# untitled.net
KiCad netlist of a schematic drawn in EAGLE
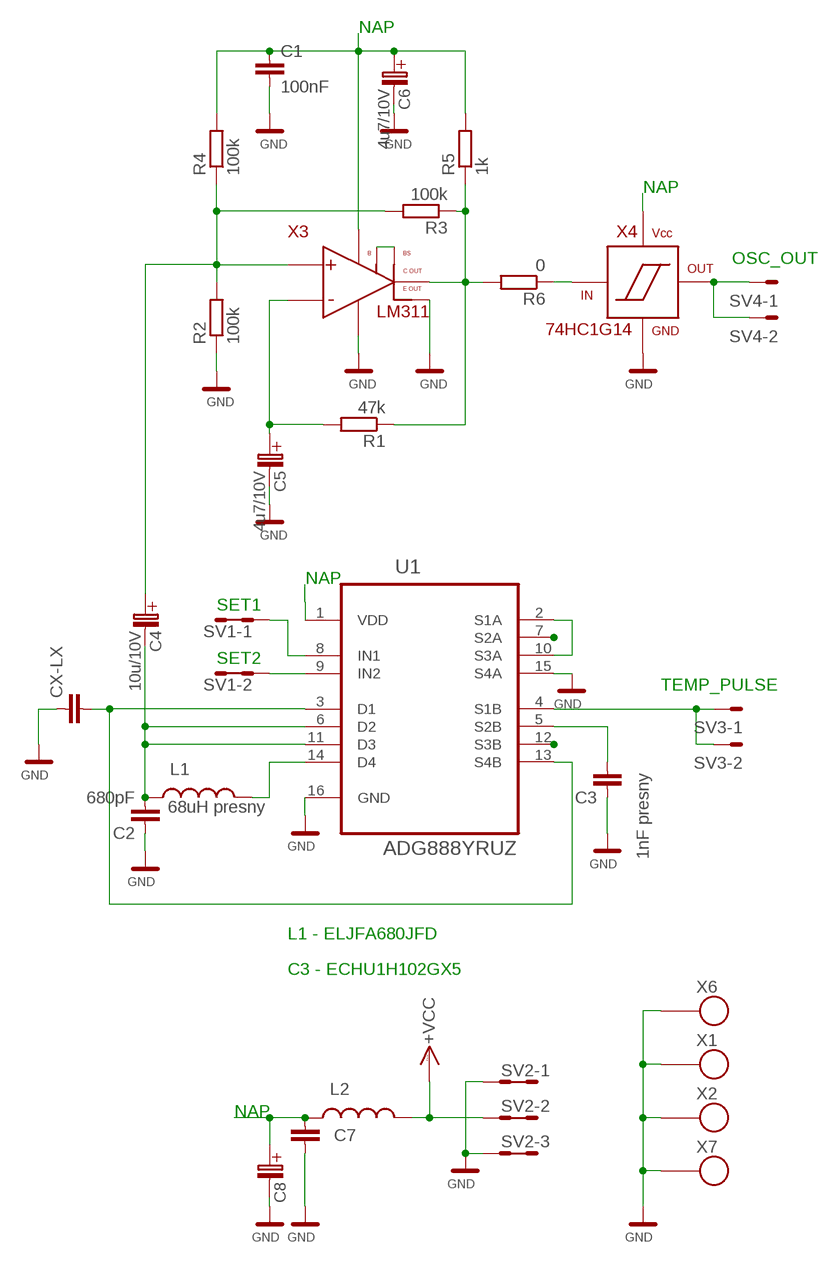
[diagram p0: schematic, sheet 1]

(export (version "E")
  (design (tool "Eeschema 10.0.6"))
  (components
    (comp (ref "C1")
      (value "100nF")
      (footprint "eagle-import:C0805")
      (libsource (lib "eagle-import") (part "C0805"))
    )
    (comp (ref "C2")
      (value "680pF")
      (footprint "eagle-import:C0805")
      (libsource (lib "eagle-import") (part "C0805"))
    )
    (comp (ref "C3")
      (value "1nF presny")
      (footprint "eagle-import:C0805")
      (libsource (lib "eagle-import") (part "C0805"))
    )
    (comp (ref "C4")
      (value "10u/10V")
      (footprint "eagle-import:B")
      (libsource (lib "eagle-import") (part "B"))
    )
    (comp (ref "C5")
      (value "4u7/10V")
      (footprint "eagle-import:B")
      (libsource (lib "eagle-import") (part "B"))
    )
    (comp (ref "C6")
      (value "4u7/10V")
      (footprint "eagle-import:B")
      (libsource (lib "eagle-import") (part "B"))
    )
    (comp (ref "C7")
      (value "C0805")
      (footprint "eagle-import:C0805")
      (libsource (lib "eagle-import") (part "C0805"))
    )
    (comp (ref "C8") (value "B") (footprint "eagle-import:B") (libsource (lib "eagle-import") (part "B")))
    (comp (ref "CX-LX")
      (value "SPEC_805")
      (footprint "eagle-import:SPEC_805")
      (libsource (lib "eagle-import") (part "SPEC_805"))
    )
    (comp (ref "L1")
      (value "68uH presny")
      (footprint "eagle-import:1210")
      (libsource (lib "eagle-import") (part "L1210"))
    )
    (comp (ref "L2")
      (value "L1210")
      (footprint "eagle-import:1210")
      (libsource (lib "eagle-import") (part "L1210"))
    )
    (comp (ref "R1")
      (value "47k")
      (footprint "eagle-import:0805")
      (libsource (lib "eagle-import") (part "R0805"))
    )
    (comp (ref "R2")
      (value "100k")
      (footprint "eagle-import:0805")
      (libsource (lib "eagle-import") (part "R0805"))
    )
    (comp (ref "R3")
      (value "100k")
      (footprint "eagle-import:0805")
      (libsource (lib "eagle-import") (part "R0805"))
    )
    (comp (ref "R4")
      (value "100k")
      (footprint "eagle-import:0805")
      (libsource (lib "eagle-import") (part "R0805"))
    )
    (comp (ref "R5")
      (value "1k")
      (footprint "eagle-import:0805")
      (libsource (lib "eagle-import") (part "R0805"))
    )
    (comp (ref "R6")
      (value "0")
      (footprint "eagle-import:0805")
      (libsource (lib "eagle-import") (part "R0805"))
    )
    (comp (ref "SV1")
      (value "MA02-2")
      (footprint "eagle-import:MA02-2")
      (libsource (lib "eagle-import") (part "MA02-2"))
    )
    (comp (ref "SV2")
      (value "MA03-2")
      (footprint "eagle-import:MA03-2")
      (libsource (lib "eagle-import") (part "MA03-2"))
    )
    (comp (ref "SV3")
      (value "MA02-1")
      (footprint "eagle-import:MA02-1")
      (libsource (lib "eagle-import") (part "MA02-1"))
    )
    (comp (ref "SV4")
      (value "MA02-1")
      (footprint "eagle-import:MA02-1")
      (libsource (lib "eagle-import") (part "MA02-1"))
    )
    (comp (ref "U1")
      (value "ADG888YRUZ")
      (footprint "eagle-import:SOP65P640X120-16N")
      (libsource (lib "eagle-import") (part "ADG888YRUZ"))
    )
    (comp (ref "X1")
      (value "SROUB3M")
      (footprint "eagle-import:SROUB3M")
      (libsource (lib "eagle-import") (part "SROUB3M"))
    )
    (comp (ref "X2")
      (value "SROUB3M")
      (footprint "eagle-import:SROUB3M")
      (libsource (lib "eagle-import") (part "SROUB3M"))
    )
    (comp (ref "X3")
      (value "LM311")
      (footprint "eagle-import:SO8")
      (libsource (lib "eagle-import") (part "LM311"))
    )
    (comp (ref "X4")
      (value "74HC1G14")
      (footprint "eagle-import:SOT353")
      (libsource (lib "eagle-import") (part "74HC1G14"))
    )
    (comp (ref "X6")
      (value "SROUB3M")
      (footprint "eagle-import:SROUB3M")
      (libsource (lib "eagle-import") (part "SROUB3M"))
    )
    (comp (ref "X7")
      (value "SROUB3M")
      (footprint "eagle-import:SROUB3M")
      (libsource (lib "eagle-import") (part "SROUB3M"))
    )
  )
  (nets
    (net (code "1") (name "+VCC") (class "Default")
      (node (ref "L2") (pin "P$2") (pinfunction "2_P$2") (pintype "passive"))
      (node (ref "SV2") (pin "3") (pinfunction "K_3") (pintype "passive"))
      (node (ref "SV2") (pin "4") (pinfunction "K_4") (pintype "passive"))
    )
    (net (code "2") (name "/NAP") (class "Default")
      (node (ref "C1") (pin "1") (pinfunction "1_1") (pintype "passive"))
      (node (ref "C6") (pin "+") (pinfunction "C_EL+_+") (pintype "passive"))
      (node (ref "C7") (pin "1") (pinfunction "1_1") (pintype "passive"))
      (node (ref "C8") (pin "+") (pinfunction "C_EL+_+") (pintype "passive"))
      (node (ref "L2") (pin "P$1") (pinfunction "1_P$1") (pintype "passive"))
      (node (ref "R4") (pin "2") (pinfunction "2_2") (pintype "passive"))
      (node (ref "R5") (pin "2") (pinfunction "2_2") (pintype "passive"))
      (node (ref "U1") (pin "1") (pinfunction "VDD_1") (pintype "power_in"))
      (node (ref "X3") (pin "8") (pinfunction "VDD_8") (pintype "bidirectional"))
      (node (ref "X4") (pin "5") (pinfunction "VCC_5") (pintype "bidirectional"))
    )
    (net (code "3") (name "GND") (class "Default")
      (node (ref "C1") (pin "2") (pinfunction "2_2") (pintype "passive"))
      (node (ref "C2") (pin "1") (pinfunction "1_1") (pintype "passive"))
      (node (ref "C3") (pin "1") (pinfunction "1_1") (pintype "passive"))
      (node (ref "C5") (pin "-") (pinfunction "C_EL-_-") (pintype "passive"))
      (node (ref "C6") (pin "-") (pinfunction "C_EL-_-") (pintype "passive"))
      (node (ref "C7") (pin "2") (pinfunction "2_2") (pintype "passive"))
      (node (ref "C8") (pin "-") (pinfunction "C_EL-_-") (pintype "passive"))
      (node (ref "CX-LX") (pin "1") (pinfunction "1_1") (pintype "passive"))
      (node (ref "R2") (pin "1") (pinfunction "1_1") (pintype "passive"))
      (node (ref "SV2") (pin "1") (pinfunction "K_1") (pintype "passive"))
      (node (ref "SV2") (pin "2") (pinfunction "K_2") (pintype "passive"))
      (node (ref "SV2") (pin "5") (pinfunction "K_5") (pintype "passive"))
      (node (ref "SV2") (pin "6") (pinfunction "K_6") (pintype "passive"))
      (node (ref "U1") (pin "15") (pinfunction "S4A_15") (pintype "bidirectional"))
      (node (ref "U1") (pin "16") (pinfunction "GND_16") (pintype "passive"))
      (node (ref "X1") (pin "P$1") (pinfunction "P$1_P$1") (pintype "bidirectional"))
      (node (ref "X2") (pin "P$1") (pinfunction "P$1_P$1") (pintype "bidirectional"))
      (node (ref "X3") (pin "1") (pinfunction "E_OUT_1") (pintype "bidirectional"))
      (node (ref "X3") (pin "4") (pinfunction "GND_4") (pintype "bidirectional"))
      (node (ref "X4") (pin "3") (pinfunction "GND_3") (pintype "bidirectional"))
      (node (ref "X6") (pin "P$1") (pinfunction "P$1_P$1") (pintype "bidirectional"))
      (node (ref "X7") (pin "P$1") (pinfunction "P$1_P$1") (pintype "bidirectional"))
    )
    (net (code "4") (name "Net-(C4-C_EL+)") (class "Default")
      (node (ref "C4") (pin "+") (pinfunction "C_EL+_+") (pintype "passive"))
      (node (ref "R2") (pin "2") (pinfunction "2_2") (pintype "passive"))
      (node (ref "R3") (pin "2") (pinfunction "2_2") (pintype "passive"))
      (node (ref "R4") (pin "1") (pinfunction "1_1") (pintype "passive"))
      (node (ref "X3") (pin "2") (pinfunction "+_2") (pintype "bidirectional"))
    )
    (net (code "5") (name "Net-(C4-C_EL-)") (class "Default")
      (node (ref "C2") (pin "2") (pinfunction "2_2") (pintype "passive"))
      (node (ref "C4") (pin "-") (pinfunction "C_EL-_-") (pintype "passive"))
      (node (ref "L1") (pin "P$1") (pinfunction "1_P$1") (pintype "passive"))
      (node (ref "U1") (pin "11") (pinfunction "D3_11") (pintype "bidirectional"))
      (node (ref "U1") (pin "6") (pinfunction "D2_6") (pintype "bidirectional"))
    )
    (net (code "6") (name "Net-(C5-C_EL+)") (class "Default")
      (node (ref "C5") (pin "+") (pinfunction "C_EL+_+") (pintype "passive"))
      (node (ref "R1") (pin "2") (pinfunction "2_2") (pintype "passive"))
      (node (ref "X3") (pin "3") (pinfunction "-_3") (pintype "bidirectional"))
    )
    (net (code "7") (name "Net-(L1-2)") (class "Default")
      (node (ref "L1") (pin "P$2") (pinfunction "2_P$2") (pintype "passive"))
      (node (ref "U1") (pin "14") (pinfunction "D4_14") (pintype "bidirectional"))
    )
    (net (code "8") (name "Net-(SV3A-P$1)") (class "Default")
      (node (ref "SV3") (pin "1") (pinfunction "P$1_1") (pintype "passive"))
      (node (ref "SV3") (pin "2") (pinfunction "P$1_2") (pintype "passive"))
      (node (ref "U1") (pin "4") (pinfunction "S1B_4") (pintype "bidirectional"))
    )
    (net (code "9") (name "Net-(SV4A-P$1)") (class "Default")
      (node (ref "SV4") (pin "1") (pinfunction "P$1_1") (pintype "passive"))
      (node (ref "SV4") (pin "2") (pinfunction "P$1_2") (pintype "passive"))
      (node (ref "X4") (pin "4") (pinfunction "OUT_4") (pintype "bidirectional"))
    )
    (net (code "10") (name "Net-(U1-D1)") (class "Default")
      (node (ref "CX-LX") (pin "2") (pinfunction "2_2") (pintype "passive"))
      (node (ref "U1") (pin "13") (pinfunction "S4B_13") (pintype "bidirectional"))
      (node (ref "U1") (pin "3") (pinfunction "D1_3") (pintype "bidirectional"))
    )
    (net (code "11") (name "Net-(U1-IN1)") (class "Default")
      (node (ref "SV1") (pin "1") (pinfunction "K_1") (pintype "passive"))
      (node (ref "SV1") (pin "2") (pinfunction "K_2") (pintype "passive"))
      (node (ref "U1") (pin "8") (pinfunction "IN1_8") (pintype "input"))
    )
    (net (code "12") (name "Net-(U1-IN2)") (class "Default")
      (node (ref "SV1") (pin "3") (pinfunction "K_3") (pintype "passive"))
      (node (ref "SV1") (pin "4") (pinfunction "K_4") (pintype "passive"))
      (node (ref "U1") (pin "9") (pinfunction "IN2_9") (pintype "input"))
    )
    (net (code "13") (name "Net-(U1-S1A)") (class "Default")
      (node (ref "U1") (pin "10") (pinfunction "S3A_10") (pintype "bidirectional"))
      (node (ref "U1") (pin "2") (pinfunction "S1A_2") (pintype "bidirectional"))
    )
    (net (code "14") (name "Net-(U1-S2B)") (class "Default")
      (node (ref "C3") (pin "2") (pinfunction "2_2") (pintype "passive"))
      (node (ref "U1") (pin "5") (pinfunction "S2B_5") (pintype "bidirectional"))
    )
    (net (code "15") (name "Net-(X3-B)") (class "Default")
      (node (ref "X3") (pin "5") (pinfunction "B_5") (pintype "bidirectional"))
      (node (ref "X3") (pin "6") (pinfunction "BS_6") (pintype "bidirectional"))
    )
    (net (code "16") (name "Net-(X3-VOUT)") (class "Default")
      (node (ref "R1") (pin "1") (pinfunction "1_1") (pintype "passive"))
      (node (ref "R3") (pin "1") (pinfunction "1_1") (pintype "passive"))
      (node (ref "R5") (pin "1") (pinfunction "1_1") (pintype "passive"))
      (node (ref "R6") (pin "2") (pinfunction "2_2") (pintype "passive"))
      (node (ref "X3") (pin "7") (pinfunction "VOUT_7") (pintype "bidirectional"))
    )
    (net (code "17") (name "Net-(X4-IN)") (class "Default")
      (node (ref "R6") (pin "1") (pinfunction "1_1") (pintype "passive"))
      (node (ref "X4") (pin "2") (pinfunction "IN_2") (pintype "bidirectional"))
    )
    (net (code "18") (name "unconnected-(U1-S2A-Pad7)") (class "Default")
      (node (ref "U1") (pin "7") (pinfunction "S2A_7") (pintype "bidirectional"))
    )
    (net (code "19") (name "unconnected-(U1-S3B-Pad12)") (class "Default")
      (node (ref "U1") (pin "12") (pinfunction "S3B_12") (pintype "bidirectional"))
    )
  )
)
